# MAX4239basedV3.net
KiCad netlist of a schematic drawn in EAGLE
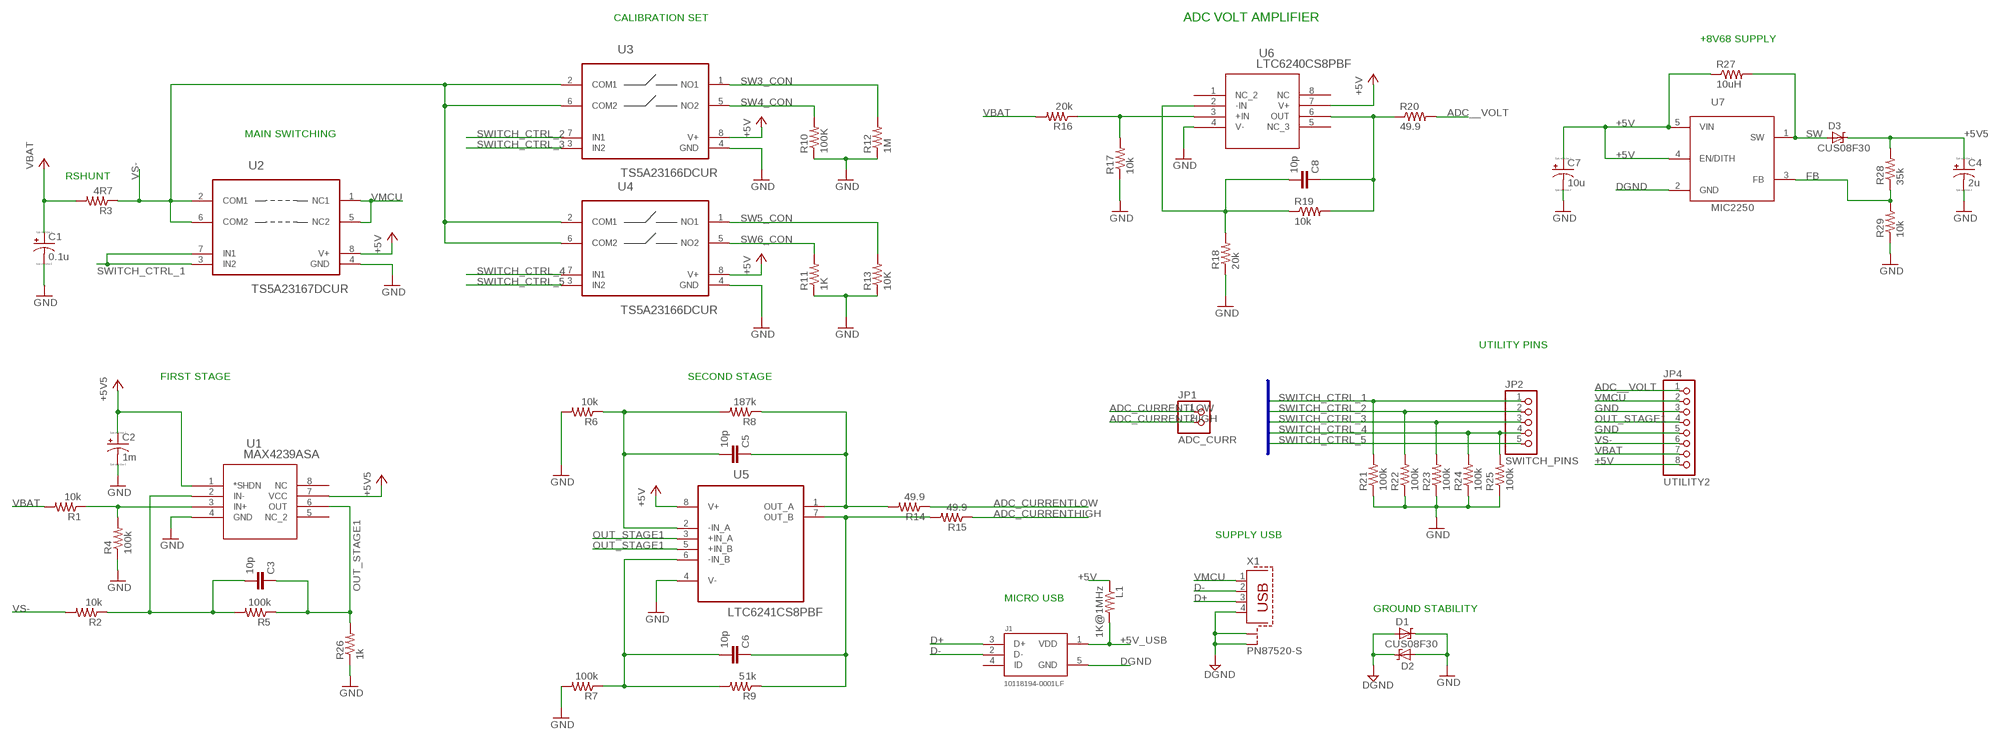
[diagram p0: schematic, sheet 1]

(export (version "E")
  (design (tool "Eeschema 10.0.6"))
  (components
    (comp (ref "C1")
      (value "0.1u")
      (footprint "eagle-import:PANASONIC_B")
      (libsource (lib "eagle-import") (part "CPOL-USB"))
    )
    (comp (ref "C2")
      (value "1m")
      (footprint "eagle-import:PANASONIC_B")
      (libsource (lib "eagle-import") (part "CPOL-USB"))
    )
    (comp (ref "C3")
      (value "10p")
      (footprint "eagle-import:C0805")
      (libsource (lib "eagle-import") (part "C-EUC0805"))
    )
    (comp (ref "C4")
      (value "2u")
      (footprint "eagle-import:PANASONIC_B")
      (libsource (lib "eagle-import") (part "CPOL-USB"))
    )
    (comp (ref "C5")
      (value "10p")
      (footprint "eagle-import:C0805")
      (libsource (lib "eagle-import") (part "C-EUC0805"))
    )
    (comp (ref "C6")
      (value "10p")
      (footprint "eagle-import:C0805")
      (libsource (lib "eagle-import") (part "C-EUC0805"))
    )
    (comp (ref "C7")
      (value "10u")
      (footprint "eagle-import:PANASONIC_B")
      (libsource (lib "eagle-import") (part "CPOL-USB"))
    )
    (comp (ref "C8")
      (value "10p")
      (footprint "eagle-import:C0805")
      (libsource (lib "eagle-import") (part "C-EUC0805"))
    )
    (comp (ref "D1")
      (value "CUS08F30")
      (footprint "eagle-import:SOD323")
      (fields (field (name "MF") "TOSHIBA"))
      (libsource (lib "eagle-import") (part "CUS08F30"))
    )
    (comp (ref "D2")
      (value "CUS08F30")
      (footprint "eagle-import:SOD323")
      (fields (field (name "MF") "TOSHIBA"))
      (libsource (lib "eagle-import") (part "CUS08F30"))
    )
    (comp (ref "D3")
      (value "CUS08F30")
      (footprint "eagle-import:SOD323")
      (fields (field (name "MF") "TOSHIBA"))
      (libsource (lib "eagle-import") (part "CUS08F30"))
    )
    (comp (ref "J1")
      (value "10118194-0001LF")
      (footprint "eagle-import:FRAMATOME_10118194-0001LF")
      (fields (field (name "MF") "Amphenol"))
      (libsource (lib "eagle-import") (part "10118194-0001LF"))
    )
    (comp (ref "JP1")
      (value "ADC_CURR")
      (footprint "eagle-import:1X02")
      (libsource (lib "eagle-import") (part "PINHD-1X2"))
    )
    (comp (ref "JP2")
      (value "SWITCH_PINS")
      (footprint "eagle-import:1X05")
      (libsource (lib "eagle-import") (part "PINHD-1X5"))
    )
    (comp (ref "JP4")
      (value "UTILITY2")
      (footprint "eagle-import:1X08")
      (libsource (lib "eagle-import") (part "PINHD-1X8"))
    )
    (comp (ref "L1")
      (value "1K@1MHz")
      (footprint "eagle-import:R0805")
      (libsource (lib "eagle-import") (part "R-US_R0805"))
    )
    (comp (ref "R1")
      (value "10k")
      (footprint "eagle-import:R0805")
      (libsource (lib "eagle-import") (part "R-US_R0805"))
    )
    (comp (ref "R2")
      (value "10k")
      (footprint "eagle-import:R0805")
      (libsource (lib "eagle-import") (part "R-US_R0805"))
    )
    (comp (ref "R3")
      (value "4R7")
      (footprint "eagle-import:R0805")
      (libsource (lib "eagle-import") (part "R-US_R0805"))
    )
    (comp (ref "R4")
      (value "100k")
      (footprint "eagle-import:R0805")
      (libsource (lib "eagle-import") (part "R-US_R0805"))
    )
    (comp (ref "R5")
      (value "100k")
      (footprint "eagle-import:R0805")
      (libsource (lib "eagle-import") (part "R-US_R0805"))
    )
    (comp (ref "R6")
      (value "10k")
      (footprint "eagle-import:R0805")
      (libsource (lib "eagle-import") (part "R-US_R0805"))
    )
    (comp (ref "R7")
      (value "100k")
      (footprint "eagle-import:R0805")
      (libsource (lib "eagle-import") (part "R-US_R0805"))
    )
    (comp (ref "R8")
      (value "187k")
      (footprint "eagle-import:R0805")
      (libsource (lib "eagle-import") (part "R-US_R0805"))
    )
    (comp (ref "R9")
      (value "51k")
      (footprint "eagle-import:R0805")
      (libsource (lib "eagle-import") (part "R-US_R0805"))
    )
    (comp (ref "R10")
      (value "100K")
      (footprint "eagle-import:R0805")
      (libsource (lib "eagle-import") (part "R-US_R0805"))
    )
    (comp (ref "R11")
      (value "1K")
      (footprint "eagle-import:R0805")
      (libsource (lib "eagle-import") (part "R-US_R0805"))
    )
    (comp (ref "R12")
      (value "1M")
      (footprint "eagle-import:R0805")
      (libsource (lib "eagle-import") (part "R-US_R0805"))
    )
    (comp (ref "R13")
      (value "10K")
      (footprint "eagle-import:R0805")
      (libsource (lib "eagle-import") (part "R-US_R0805"))
    )
    (comp (ref "R14")
      (value "49.9")
      (footprint "eagle-import:R0805")
      (libsource (lib "eagle-import") (part "R-US_R0805"))
    )
    (comp (ref "R15")
      (value "49.9")
      (footprint "eagle-import:R0805")
      (libsource (lib "eagle-import") (part "R-US_R0805"))
    )
    (comp (ref "R16")
      (value "20k")
      (footprint "eagle-import:R0805")
      (libsource (lib "eagle-import") (part "R-US_R0805"))
    )
    (comp (ref "R17")
      (value "10k")
      (footprint "eagle-import:R0805")
      (libsource (lib "eagle-import") (part "R-US_R0805"))
    )
    (comp (ref "R18")
      (value "20k")
      (footprint "eagle-import:R0805")
      (libsource (lib "eagle-import") (part "R-US_R0805"))
    )
    (comp (ref "R19")
      (value "10k")
      (footprint "eagle-import:R0805")
      (libsource (lib "eagle-import") (part "R-US_R0805"))
    )
    (comp (ref "R20")
      (value "49.9")
      (footprint "eagle-import:R0805")
      (libsource (lib "eagle-import") (part "R-US_R0805"))
    )
    (comp (ref "R21")
      (value "100k")
      (footprint "eagle-import:R0805")
      (libsource (lib "eagle-import") (part "R-US_R0805"))
    )
    (comp (ref "R22")
      (value "100k")
      (footprint "eagle-import:R0805")
      (libsource (lib "eagle-import") (part "R-US_R0805"))
    )
    (comp (ref "R23")
      (value "100k")
      (footprint "eagle-import:R0805")
      (libsource (lib "eagle-import") (part "R-US_R0805"))
    )
    (comp (ref "R24")
      (value "100k")
      (footprint "eagle-import:R0805")
      (libsource (lib "eagle-import") (part "R-US_R0805"))
    )
    (comp (ref "R25")
      (value "100k")
      (footprint "eagle-import:R0805")
      (libsource (lib "eagle-import") (part "R-US_R0805"))
    )
    (comp (ref "R26")
      (value "1k")
      (footprint "eagle-import:R0805")
      (libsource (lib "eagle-import") (part "R-US_R0805"))
    )
    (comp (ref "R27")
      (value "10uH")
      (footprint "eagle-import:R1210")
      (libsource (lib "eagle-import") (part "R-US_R1210"))
    )
    (comp (ref "R28")
      (value "35k")
      (footprint "eagle-import:R0805")
      (libsource (lib "eagle-import") (part "R-US_R0805"))
    )
    (comp (ref "R29")
      (value "10k")
      (footprint "eagle-import:R0805")
      (libsource (lib "eagle-import") (part "R-US_R0805"))
    )
    (comp (ref "U1")
      (value "MAX4239ASA")
      (footprint "eagle-import:21-0041B_8")
      (fields (field (name "MF") "Maxim Integrated") (field (name "MP") "MAX4239ASA+"))
      (libsource (lib "eagle-import") (part "MAX4239ASA"))
    )
    (comp (ref "U2")
      (value "TS5A23167DCUR")
      (footprint "eagle-import:SOP50P310X90-8N")
      (fields (field (name "MF") "Texas Instruments"))
      (libsource (lib "eagle-import") (part "TS5A23167DCUR"))
    )
    (comp (ref "U3")
      (value "TS5A23166DCUR")
      (footprint "eagle-import:SOP50P310X90-8N")
      (fields (field (name "MF") "Texas Instruments"))
      (libsource (lib "eagle-import") (part "TS5A23166DCUR"))
    )
    (comp (ref "U4")
      (value "TS5A23166DCUR")
      (footprint "eagle-import:SOP50P310X90-8N")
      (fields (field (name "MF") "Texas Instruments"))
      (libsource (lib "eagle-import") (part "TS5A23166DCUR"))
    )
    (comp (ref "U5")
      (value "LTC6241CS8PBF")
      (footprint "eagle-import:SOIC127P600X175-8N")
      (fields (field (name "MF") "Linear Technology") (field (name "MP") "LTC6241CS8#PBF"))
      (libsource (lib "eagle-import") (part "LTC6241CS8PBF"))
    )
    (comp (ref "U6")
      (value "LTC6240CS8PBF")
      (footprint "eagle-import:SO-8_S")
      (fields (field (name "MF") "Linear Technology") (field (name "MP") "LTC6240CS8#PBF"))
      (libsource (lib "eagle-import") (part "LTC6240CS8PBF"))
    )
    (comp (ref "U7")
      (value "MIC2250")
      (footprint "eagle-import:SOT95P270X145-5N")
      (fields (field (name "MF") "MICROCHIP"))
      (libsource (lib "eagle-import") (part "MIC2250"))
    )
    (comp (ref "X1")
      (value "PN87520-S")
      (footprint "eagle-import:PN87520-S")
      (libsource (lib "eagle-import") (part "PN87520-S"))
    )
  )
  (nets
    (net (code "1") (name "+5V") (class "Default")
      (node (ref "C7") (pin "+") (pinfunction "+_+") (pintype "passive"))
      (node (ref "JP4") (pin "8") (pinfunction "8_8") (pintype "passive"))
      (node (ref "L1") (pin "1") (pinfunction "1_1") (pintype "passive"))
      (node (ref "R27") (pin "1") (pinfunction "1_1") (pintype "passive"))
      (node (ref "U2") (pin "8") (pinfunction "V+_8") (pintype "power_in"))
      (node (ref "U3") (pin "8") (pinfunction "V+_8") (pintype "power_in"))
      (node (ref "U4") (pin "8") (pinfunction "V+_8") (pintype "power_in"))
      (node (ref "U5") (pin "8") (pinfunction "V+_8") (pintype "power_in"))
      (node (ref "U6") (pin "7") (pinfunction "V+_7") (pintype "power_in"))
      (node (ref "U7") (pin "4") (pinfunction "EN/DITH_4") (pintype "bidirectional"))
      (node (ref "U7") (pin "5") (pinfunction "VIN_5") (pintype "bidirectional"))
    )
    (net (code "2") (name "+5V5") (class "Default")
      (node (ref "C2") (pin "+") (pinfunction "+_+") (pintype "passive"))
      (node (ref "C4") (pin "+") (pinfunction "+_+") (pintype "passive"))
      (node (ref "D3") (pin "C") (pinfunction "C_C") (pintype "passive"))
      (node (ref "R28") (pin "2") (pinfunction "2_2") (pintype "passive"))
      (node (ref "U1") (pin "1") (pinfunction "*SHDN_1") (pintype "passive"))
      (node (ref "U1") (pin "7") (pinfunction "VCC_7") (pintype "power_in"))
    )
    (net (code "3") (name "/+5V_USB") (class "Default")
      (node (ref "J1") (pin "1") (pinfunction "VDD_1") (pintype "power_in"))
      (node (ref "L1") (pin "2") (pinfunction "2_2") (pintype "passive"))
    )
    (net (code "4") (name "/ADC_CURRENTHIGH") (class "Default")
      (node (ref "JP1") (pin "2") (pinfunction "2_2") (pintype "passive"))
      (node (ref "R15") (pin "1") (pinfunction "1_1") (pintype "passive"))
    )
    (net (code "5") (name "/ADC_CURRENTLOW") (class "Default")
      (node (ref "JP1") (pin "1") (pinfunction "1_1") (pintype "passive"))
      (node (ref "R14") (pin "1") (pinfunction "1_1") (pintype "passive"))
    )
    (net (code "6") (name "/ADC__VOLT") (class "Default")
      (node (ref "JP4") (pin "1") (pinfunction "1_1") (pintype "passive"))
      (node (ref "R20") (pin "2") (pinfunction "2_2") (pintype "passive"))
    )
    (net (code "7") (name "/D+") (class "Default")
      (node (ref "J1") (pin "3") (pinfunction "D+_3") (pintype "bidirectional"))
      (node (ref "X1") (pin "3") (pinfunction "3_3") (pintype "passive"))
    )
    (net (code "8") (name "/D-") (class "Default")
      (node (ref "J1") (pin "2") (pinfunction "D-_2") (pintype "bidirectional"))
      (node (ref "X1") (pin "2") (pinfunction "2_2") (pintype "passive"))
    )
    (net (code "9") (name "/FB") (class "Default")
      (node (ref "R28") (pin "1") (pinfunction "1_1") (pintype "passive"))
      (node (ref "R29") (pin "2") (pinfunction "2_2") (pintype "passive"))
      (node (ref "U7") (pin "3") (pinfunction "FB_3") (pintype "bidirectional"))
    )
    (net (code "10") (name "/OUT_STAGE1") (class "Default")
      (node (ref "C3") (pin "1") (pinfunction "1_1") (pintype "passive"))
      (node (ref "JP4") (pin "4") (pinfunction "4_4") (pintype "passive"))
      (node (ref "R26") (pin "2") (pinfunction "2_2") (pintype "passive"))
      (node (ref "R5") (pin "1") (pinfunction "1_1") (pintype "passive"))
      (node (ref "U1") (pin "6") (pinfunction "OUT_6") (pintype "output"))
      (node (ref "U5") (pin "3") (pinfunction "+IN_A_3") (pintype "input"))
      (node (ref "U5") (pin "5") (pinfunction "+IN_B_5") (pintype "input"))
    )
    (net (code "11") (name "/SW") (class "Default")
      (node (ref "D3") (pin "A") (pinfunction "A_A") (pintype "passive"))
      (node (ref "R27") (pin "2") (pinfunction "2_2") (pintype "passive"))
      (node (ref "U7") (pin "1") (pinfunction "SW_1") (pintype "bidirectional"))
    )
    (net (code "12") (name "/SW3_CON") (class "Default")
      (node (ref "R12") (pin "2") (pinfunction "2_2") (pintype "passive"))
      (node (ref "U3") (pin "1") (pinfunction "NO1_1") (pintype "bidirectional"))
    )
    (net (code "13") (name "/SW4_CON") (class "Default")
      (node (ref "R10") (pin "2") (pinfunction "2_2") (pintype "passive"))
      (node (ref "U3") (pin "5") (pinfunction "NO2_5") (pintype "bidirectional"))
    )
    (net (code "14") (name "/SW5_CON") (class "Default")
      (node (ref "R13") (pin "2") (pinfunction "2_2") (pintype "passive"))
      (node (ref "U4") (pin "1") (pinfunction "NO1_1") (pintype "bidirectional"))
    )
    (net (code "15") (name "/SW6_CON") (class "Default")
      (node (ref "R11") (pin "2") (pinfunction "2_2") (pintype "passive"))
      (node (ref "U4") (pin "5") (pinfunction "NO2_5") (pintype "bidirectional"))
    )
    (net (code "16") (name "/SWITCH_CTRL_1") (class "Default")
      (node (ref "JP2") (pin "1") (pinfunction "1_1") (pintype "passive"))
      (node (ref "R21") (pin "2") (pinfunction "2_2") (pintype "passive"))
      (node (ref "U2") (pin "3") (pinfunction "IN2_3") (pintype "input"))
      (node (ref "U2") (pin "7") (pinfunction "IN1_7") (pintype "input"))
    )
    (net (code "17") (name "/SWITCH_CTRL_2") (class "Default")
      (node (ref "JP2") (pin "2") (pinfunction "2_2") (pintype "passive"))
      (node (ref "R22") (pin "2") (pinfunction "2_2") (pintype "passive"))
      (node (ref "U3") (pin "7") (pinfunction "IN1_7") (pintype "input"))
    )
    (net (code "18") (name "/SWITCH_CTRL_3") (class "Default")
      (node (ref "JP2") (pin "3") (pinfunction "3_3") (pintype "passive"))
      (node (ref "R23") (pin "2") (pinfunction "2_2") (pintype "passive"))
      (node (ref "U3") (pin "3") (pinfunction "IN2_3") (pintype "input"))
    )
    (net (code "19") (name "/SWITCH_CTRL_4") (class "Default")
      (node (ref "JP2") (pin "4") (pinfunction "4_4") (pintype "passive"))
      (node (ref "R24") (pin "2") (pinfunction "2_2") (pintype "passive"))
      (node (ref "R25") (pin "2") (pinfunction "2_2") (pintype "passive"))
      (node (ref "U4") (pin "7") (pinfunction "IN1_7") (pintype "input"))
    )
    (net (code "20") (name "/SWITCH_CTRL_5") (class "Default")
      (node (ref "JP2") (pin "5") (pinfunction "5_5") (pintype "passive"))
      (node (ref "U4") (pin "3") (pinfunction "IN2_3") (pintype "input"))
    )
    (net (code "21") (name "/VMCU") (class "Default")
      (node (ref "JP4") (pin "2") (pinfunction "2_2") (pintype "passive"))
      (node (ref "U2") (pin "1") (pinfunction "NC1_1") (pintype "bidirectional"))
      (node (ref "U2") (pin "5") (pinfunction "NC2_5") (pintype "bidirectional"))
      (node (ref "X1") (pin "1") (pinfunction "1_1") (pintype "passive"))
    )
    (net (code "22") (name "/VS-") (class "Default")
      (node (ref "JP4") (pin "6") (pinfunction "6_6") (pintype "passive"))
      (node (ref "R2") (pin "2") (pinfunction "2_2") (pintype "passive"))
      (node (ref "R3") (pin "1") (pinfunction "1_1") (pintype "passive"))
      (node (ref "U2") (pin "2") (pinfunction "COM1_2") (pintype "bidirectional"))
      (node (ref "U2") (pin "6") (pinfunction "COM2_6") (pintype "bidirectional"))
      (node (ref "U3") (pin "2") (pinfunction "COM1_2") (pintype "bidirectional"))
      (node (ref "U3") (pin "6") (pinfunction "COM2_6") (pintype "bidirectional"))
      (node (ref "U4") (pin "2") (pinfunction "COM1_2") (pintype "bidirectional"))
      (node (ref "U4") (pin "6") (pinfunction "COM2_6") (pintype "bidirectional"))
    )
    (net (code "23") (name "DGND") (class "Default")
      (node (ref "D1") (pin "A") (pinfunction "A_A") (pintype "passive"))
      (node (ref "D2") (pin "C") (pinfunction "C_C") (pintype "passive"))
      (node (ref "J1") (pin "5") (pinfunction "GND_5") (pintype "power_in"))
      (node (ref "U7") (pin "2") (pinfunction "GND_2") (pintype "bidirectional"))
      (node (ref "X1") (pin "4") (pinfunction "4_4") (pintype "passive"))
      (node (ref "X1") (pin "S1") (pinfunction "S1_S1") (pintype "passive"))
      (node (ref "X1") (pin "S2") (pinfunction "S2_S2") (pintype "passive"))
    )
    (net (code "24") (name "GND") (class "Default")
      (node (ref "C1") (pin "-") (pinfunction "-_-") (pintype "passive"))
      (node (ref "C2") (pin "-") (pinfunction "-_-") (pintype "passive"))
      (node (ref "C4") (pin "-") (pinfunction "-_-") (pintype "passive"))
      (node (ref "C7") (pin "-") (pinfunction "-_-") (pintype "passive"))
      (node (ref "D1") (pin "C") (pinfunction "C_C") (pintype "passive"))
      (node (ref "D2") (pin "A") (pinfunction "A_A") (pintype "passive"))
      (node (ref "JP4") (pin "3") (pinfunction "3_3") (pintype "passive"))
      (node (ref "JP4") (pin "5") (pinfunction "5_5") (pintype "passive"))
      (node (ref "R10") (pin "1") (pinfunction "1_1") (pintype "passive"))
      (node (ref "R11") (pin "1") (pinfunction "1_1") (pintype "passive"))
      (node (ref "R12") (pin "1") (pinfunction "1_1") (pintype "passive"))
      (node (ref "R13") (pin "1") (pinfunction "1_1") (pintype "passive"))
      (node (ref "R17") (pin "1") (pinfunction "1_1") (pintype "passive"))
      (node (ref "R18") (pin "1") (pinfunction "1_1") (pintype "passive"))
      (node (ref "R21") (pin "1") (pinfunction "1_1") (pintype "passive"))
      (node (ref "R22") (pin "1") (pinfunction "1_1") (pintype "passive"))
      (node (ref "R23") (pin "1") (pinfunction "1_1") (pintype "passive"))
      (node (ref "R24") (pin "1") (pinfunction "1_1") (pintype "passive"))
      (node (ref "R25") (pin "1") (pinfunction "1_1") (pintype "passive"))
      (node (ref "R26") (pin "1") (pinfunction "1_1") (pintype "passive"))
      (node (ref "R29") (pin "1") (pinfunction "1_1") (pintype "passive"))
      (node (ref "R4") (pin "1") (pinfunction "1_1") (pintype "passive"))
      (node (ref "R6") (pin "2") (pinfunction "2_2") (pintype "passive"))
      (node (ref "R7") (pin "2") (pinfunction "2_2") (pintype "passive"))
      (node (ref "U1") (pin "4") (pinfunction "GND_4") (pintype "power_in"))
      (node (ref "U2") (pin "4") (pinfunction "GND_4") (pintype "passive"))
      (node (ref "U3") (pin "4") (pinfunction "GND_4") (pintype "passive"))
      (node (ref "U4") (pin "4") (pinfunction "GND_4") (pintype "passive"))
      (node (ref "U5") (pin "4") (pinfunction "V-_4") (pintype "power_in"))
      (node (ref "U6") (pin "4") (pinfunction "V-_4") (pintype "power_in"))
    )
    (net (code "25") (name "Net-(U1-IN+)") (class "Default")
      (node (ref "R1") (pin "1") (pinfunction "1_1") (pintype "passive"))
      (node (ref "R4") (pin "2") (pinfunction "2_2") (pintype "passive"))
      (node (ref "U1") (pin "3") (pinfunction "IN+_3") (pintype "input"))
    )
    (net (code "26") (name "Net-(U1-IN-)") (class "Default")
      (node (ref "C3") (pin "2") (pinfunction "2_2") (pintype "passive"))
      (node (ref "R2") (pin "1") (pinfunction "1_1") (pintype "passive"))
      (node (ref "R5") (pin "2") (pinfunction "2_2") (pintype "passive"))
      (node (ref "U1") (pin "2") (pinfunction "IN-_2") (pintype "input"))
    )
    (net (code "27") (name "Net-(U5--IN_A)") (class "Default")
      (node (ref "C5") (pin "2") (pinfunction "2_2") (pintype "passive"))
      (node (ref "R6") (pin "1") (pinfunction "1_1") (pintype "passive"))
      (node (ref "R8") (pin "2") (pinfunction "2_2") (pintype "passive"))
      (node (ref "U5") (pin "2") (pinfunction "-IN_A_2") (pintype "input"))
    )
    (net (code "28") (name "Net-(U5--IN_B)") (class "Default")
      (node (ref "C6") (pin "2") (pinfunction "2_2") (pintype "passive"))
      (node (ref "R7") (pin "1") (pinfunction "1_1") (pintype "passive"))
      (node (ref "R9") (pin "2") (pinfunction "2_2") (pintype "passive"))
      (node (ref "U5") (pin "6") (pinfunction "-IN_B_6") (pintype "input"))
    )
    (net (code "29") (name "Net-(U5-OUT_A)") (class "Default")
      (node (ref "C5") (pin "1") (pinfunction "1_1") (pintype "passive"))
      (node (ref "R14") (pin "2") (pinfunction "2_2") (pintype "passive"))
      (node (ref "R8") (pin "1") (pinfunction "1_1") (pintype "passive"))
      (node (ref "U5") (pin "1") (pinfunction "OUT_A_1") (pintype "output"))
    )
    (net (code "30") (name "Net-(U5-OUT_B)") (class "Default")
      (node (ref "C6") (pin "1") (pinfunction "1_1") (pintype "passive"))
      (node (ref "R15") (pin "2") (pinfunction "2_2") (pintype "passive"))
      (node (ref "R9") (pin "1") (pinfunction "1_1") (pintype "passive"))
      (node (ref "U5") (pin "7") (pinfunction "OUT_B_7") (pintype "output"))
    )
    (net (code "31") (name "Net-(U6-+IN)") (class "Default")
      (node (ref "R16") (pin "1") (pinfunction "1_1") (pintype "passive"))
      (node (ref "R17") (pin "2") (pinfunction "2_2") (pintype "passive"))
      (node (ref "U6") (pin "3") (pinfunction "+IN_3") (pintype "input"))
    )
    (net (code "32") (name "Net-(U6--IN)") (class "Default")
      (node (ref "C8") (pin "2") (pinfunction "2_2") (pintype "passive"))
      (node (ref "R18") (pin "2") (pinfunction "2_2") (pintype "passive"))
      (node (ref "R19") (pin "1") (pinfunction "1_1") (pintype "passive"))
      (node (ref "U6") (pin "2") (pinfunction "-IN_2") (pintype "input"))
    )
    (net (code "33") (name "Net-(U6-OUT)") (class "Default")
      (node (ref "C8") (pin "1") (pinfunction "1_1") (pintype "passive"))
      (node (ref "R19") (pin "2") (pinfunction "2_2") (pintype "passive"))
      (node (ref "R20") (pin "1") (pinfunction "1_1") (pintype "passive"))
      (node (ref "U6") (pin "6") (pinfunction "OUT_6") (pintype "output"))
    )
    (net (code "34") (name "VBAT") (class "Default")
      (node (ref "C1") (pin "+") (pinfunction "+_+") (pintype "passive"))
      (node (ref "JP4") (pin "7") (pinfunction "7_7") (pintype "passive"))
      (node (ref "R1") (pin "2") (pinfunction "2_2") (pintype "passive"))
      (node (ref "R16") (pin "2") (pinfunction "2_2") (pintype "passive"))
      (node (ref "R3") (pin "2") (pinfunction "2_2") (pintype "passive"))
    )
    (net (code "35") (name "unconnected-(J1-ID-Pad4)") (class "Default")
      (node (ref "J1") (pin "4") (pinfunction "ID_4") (pintype "passive"))
    )
    (net (code "36") (name "unconnected-(U1-NC-Pad8)") (class "Default")
      (node (ref "U1") (pin "8") (pinfunction "NC_8") (pintype "passive"))
    )
    (net (code "37") (name "unconnected-(U1-NC_2-Pad5)") (class "Default")
      (node (ref "U1") (pin "5") (pinfunction "NC_2_5") (pintype "passive"))
    )
    (net (code "38") (name "unconnected-(U6-NC-Pad8)") (class "Default")
      (node (ref "U6") (pin "8") (pinfunction "NC_8") (pintype "no_connect"))
    )
    (net (code "39") (name "unconnected-(U6-NC_2-Pad1)") (class "Default")
      (node (ref "U6") (pin "1") (pinfunction "NC_2_1") (pintype "no_connect"))
    )
    (net (code "40") (name "unconnected-(U6-NC_3-Pad5)") (class "Default")
      (node (ref "U6") (pin "5") (pinfunction "NC_3_5") (pintype "no_connect"))
    )
  )
)
